# MCU.net
KiCad netlist of a schematic drawn in Altium Designer
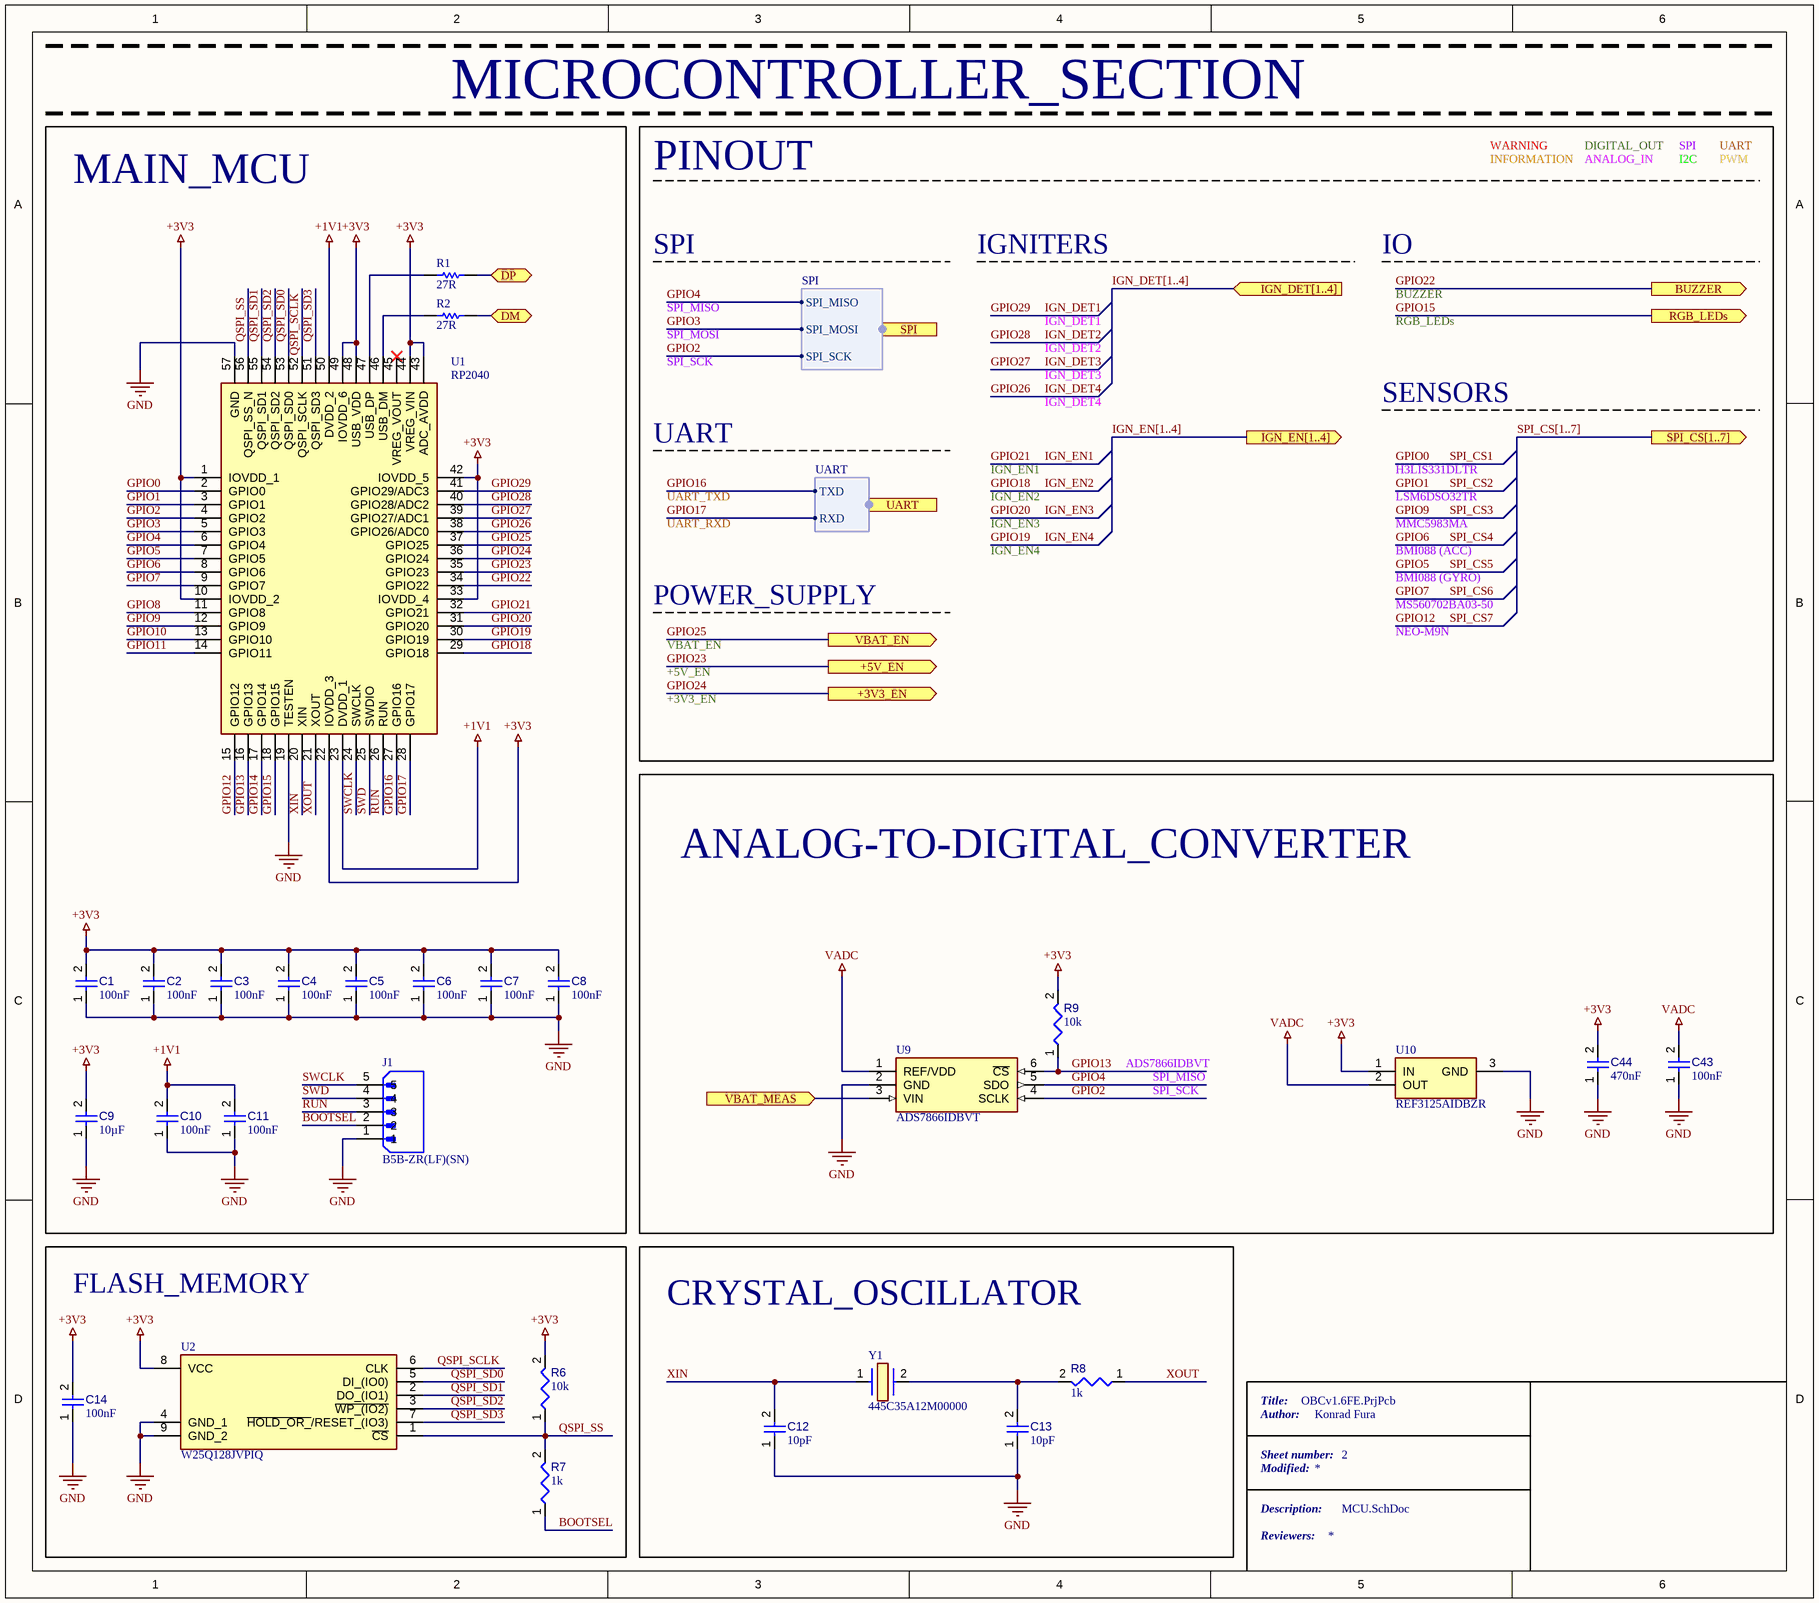
[diagram p0: MCU.SchDoc]

(export (version "E")
  (design (tool "Eeschema 10.0.6"))
  (components
    (comp (ref "C1")
      (value "100nF")
      (footprint "CAPC0402(1005)60_L")
      (description "Chip Capacitor, 100nF +/-20%, 10V, 0402, Thickness 0.6 mm")
      (fields (field (name "TOLERANCE") "20%") (field (name "Comment") "Capacitor 100nF +/-20% 10V 0402"))
      (libsource (lib "PWr in Space team") (part "CAP-NP-2"))
    )
    (comp (ref "C2")
      (value "100nF")
      (footprint "CAPC0402(1005)60_L")
      (description "Chip Capacitor, 100nF +/-20%, 10V, 0402, Thickness 0.6 mm")
      (fields (field (name "TOLERANCE") "20%") (field (name "Comment") "Capacitor 100nF +/-20% 10V 0402"))
      (libsource (lib "PWr in Space team") (part "CAP-NP-2"))
    )
    (comp (ref "C3")
      (value "100nF")
      (footprint "CAPC0402(1005)60_L")
      (description "Chip Capacitor, 100nF +/-20%, 10V, 0402, Thickness 0.6 mm")
      (fields (field (name "TOLERANCE") "20%") (field (name "Comment") "Capacitor 100nF +/-20% 10V 0402"))
      (libsource (lib "PWr in Space team") (part "CAP-NP-2"))
    )
    (comp (ref "C4")
      (value "100nF")
      (footprint "CAPC0402(1005)60_L")
      (description "Chip Capacitor, 100nF +/-20%, 10V, 0402, Thickness 0.6 mm")
      (fields (field (name "TOLERANCE") "20%") (field (name "Comment") "Capacitor 100nF +/-20% 10V 0402"))
      (libsource (lib "PWr in Space team") (part "CAP-NP-2"))
    )
    (comp (ref "C5")
      (value "100nF")
      (footprint "CAPC0402(1005)60_L")
      (description "Chip Capacitor, 100nF +/-20%, 10V, 0402, Thickness 0.6 mm")
      (fields (field (name "TOLERANCE") "20%") (field (name "Comment") "Capacitor 100nF +/-20% 10V 0402"))
      (libsource (lib "PWr in Space team") (part "CAP-NP-2"))
    )
    (comp (ref "C6")
      (value "100nF")
      (footprint "CAPC0402(1005)60_L")
      (description "Chip Capacitor, 100nF +/-20%, 10V, 0402, Thickness 0.6 mm")
      (fields (field (name "TOLERANCE") "20%") (field (name "Comment") "Capacitor 100nF +/-20% 10V 0402"))
      (libsource (lib "PWr in Space team") (part "CAP-NP-2"))
    )
    (comp (ref "C7")
      (value "100nF")
      (footprint "CAPC0402(1005)60_L")
      (description "Chip Capacitor, 100nF +/-20%, 10V, 0402, Thickness 0.6 mm")
      (fields (field (name "TOLERANCE") "20%") (field (name "Comment") "Capacitor 100nF +/-20% 10V 0402"))
      (libsource (lib "PWr in Space team") (part "CAP-NP-2"))
    )
    (comp (ref "C8")
      (value "100nF")
      (footprint "CAPC0402(1005)60_L")
      (description "Chip Capacitor, 100nF +/-20%, 10V, 0402, Thickness 0.6 mm")
      (fields (field (name "TOLERANCE") "20%") (field (name "Comment") "Capacitor 100nF +/-20% 10V 0402"))
      (libsource (lib "PWr in Space team") (part "CAP-NP-2"))
    )
    (comp (ref "C9")
      (value "10µF")
      (footprint "CAPC3216X180X50NL20T25")
      (description "Chip Capacitor, 10 uF, +/- 10%, 16 V, 1206 (3216 Metric)")
      (fields (field (name "TOLERANCE") "10%") (field (name "Comment") "Capacitor 10 uF +/- 10% 16 V 1206"))
      (libsource (lib "PWr in Space team") (part "CAP-NP-2"))
    )
    (comp (ref "C10")
      (value "100nF")
      (footprint "CAPC0402(1005)60_L")
      (description "Chip Capacitor, 100nF +/-20%, 10V, 0402, Thickness 0.6 mm")
      (fields (field (name "TOLERANCE") "20%") (field (name "Comment") "Capacitor 100nF +/-20% 10V 0402"))
      (libsource (lib "PWr in Space team") (part "CAP-NP-2"))
    )
    (comp (ref "C11")
      (value "100nF")
      (footprint "CAPC0402(1005)60_L")
      (description "Chip Capacitor, 100nF +/-20%, 10V, 0402, Thickness 0.6 mm")
      (fields (field (name "TOLERANCE") "20%") (field (name "Comment") "Capacitor 100nF +/-20% 10V 0402"))
      (libsource (lib "PWr in Space team") (part "CAP-NP-2"))
    )
    (comp (ref "C12")
      (value "10pF")
      (footprint "CAPC1005X55X30LL05T10")
      (description "Chip Capacitor, 10 pF, +/- 0.25 pF, 50 V, 0402 (1005 Metric)")
      (fields
        (field (name "TOLERANCE") "0.25%")
        (field (name "Comment") "Capacitor 10 pF +/- 0.25 pF 50 V 0402")
      )
      (libsource (lib "PWr in Space team") (part "CAP-NP-2"))
    )
    (comp (ref "C13")
      (value "10pF")
      (footprint "CAPC1005X55X30LL05T10")
      (description "Chip Capacitor, 10 pF, +/- 0.25 pF, 50 V, 0402 (1005 Metric)")
      (fields
        (field (name "TOLERANCE") "0.25%")
        (field (name "Comment") "Capacitor 10 pF +/- 0.25 pF 50 V 0402")
      )
      (libsource (lib "PWr in Space team") (part "CAP-NP-2"))
    )
    (comp (ref "C14")
      (value "100nF")
      (footprint "CAPC0402(1005)60_L")
      (description "Chip Capacitor, 100nF +/-20%, 10V, 0402, Thickness 0.6 mm")
      (fields (field (name "TOLERANCE") "20%") (field (name "Comment") "Capacitor 100nF +/-20% 10V 0402"))
      (libsource (lib "PWr in Space team") (part "CAP-NP-2"))
    )
    (comp (ref "C43")
      (value "100nF")
      (footprint "CAPC0402(1005)60_L")
      (description "Chip Capacitor, 100nF +/-20%, 10V, 0402, Thickness 0.6 mm")
      (fields (field (name "TOLERANCE") "20%") (field (name "Comment") "Capacitor 100nF +/-20% 10V 0402"))
      (libsource (lib "PWr in Space team") (part "CAP-NP-2"))
    )
    (comp (ref "C44")
      (value "470nF")
      (footprint "CAPC0402(1005)60_L")
      (description "Chip Capacitor, 470nF +/-40%, 10V, 0402, Thickness 0.6 mm")
      (fields (field (name "TOLERANCE") "20%") (field (name "Comment") "Capacitor 470nF +/-40% 10V 0402"))
      (libsource (lib "PWr in Space team") (part "CAP-NP-2"))
    )
    (comp (ref "J1")
      (value "B5B-ZR(LF)(SN)")
      (footprint "JST_B5B-ZR(LF)(SN)")
      (fields (field (name "MF") "{'manufacturer': u'JST'}"))
      (libsource (lib "SnapEDA_Library") (part "B5B-ZR(LF)(SN)"))
    )
    (comp (ref "R1")
      (value "27R")
      (footprint "RESC1005X40X25NL05T05")
      (fields (field (name "MANUFACTURER") "Vishay Dale") (field (name "PART NUMBER") "CRCW040227R0JNED"))
      (libsource (lib "Altium Content Vault") (part "RES"))
    )
    (comp (ref "R2")
      (value "27R")
      (footprint "RESC1005X40X25NL05T05")
      (fields (field (name "MANUFACTURER") "Vishay Dale") (field (name "PART NUMBER") "CRCW040227R0JNED"))
      (libsource (lib "Altium Content Vault") (part "RES"))
    )
    (comp (ref "R6")
      (value "10k")
      (footprint "RESC0402(1005)_L")
      (description "Chip Resistor, 10 kOhms, +/-1 %, 63 mW, -55 to 125 degC, 0402")
      (fields (field (name "POWER") "63mW") (field (name "TOLERANCE") "1%"))
      (libsource (lib "PWr in Space team") (part "RES-2"))
    )
    (comp (ref "R7")
      (value "1k")
      (footprint "RESC0402(1005)_L")
      (description "Chip Resistor, 1 kOhms, +/-5 %, 63 mW, -55 to 155 degC, 0402")
      (fields (field (name "TOLERANCE") "5%") (field (name "POWER") "63mW"))
      (libsource (lib "PWr in Space team") (part "RES-2"))
    )
    (comp (ref "R8")
      (value "1k")
      (footprint "RESC0402(1005)_L")
      (description "Chip Resistor, 1 kOhms, +/-5 %, 63 mW, -55 to 155 degC, 0402")
      (fields (field (name "TOLERANCE") "5%") (field (name "POWER") "63mW"))
      (libsource (lib "PWr in Space team") (part "RES-2"))
    )
    (comp (ref "R9")
      (value "10k")
      (footprint "RESC0402(1005)_L")
      (description "Chip Resistor, 10 kOhms, +/-1 %, 63 mW, -55 to 125 degC, 0402")
      (fields (field (name "POWER") "63mW") (field (name "TOLERANCE") "1%"))
      (libsource (lib "PWr in Space team") (part "RES-2"))
    )
    (comp (ref "U1")
      (value "RP2040")
      (footprint "QFN40P700X700X90-57N-D")
      (description "Integrated Circuit")
      (fields
        (field (name "MANUFACTURER_PART_NUMBER") "RPI Chip RP2040-10-10")
        (field (name "MOUSER PART NUMBER") "358-RP2040CHIP-10-10")
      )
      (libsource (lib "PWr in Space team") (part "RPI_Chip_RP2040-10-10"))
    )
    (comp (ref "U2")
      (value "W25Q128JVPIQ")
      (footprint "SamacSys:SON127P600X500X80-9N-D")
      (description "Integrated Circuit")
      (fields (field (name "MOUSER PART NUMBER") "454-W25Q128JVPIQ"))
      (libsource (lib "*") (part "W25Q128JVPIQ"))
    )
    (comp (ref "U9")
      (value "ADS7866IDBVT")
      (footprint "SamacSys:SOT95P280X145-6N")
      (description "Integrated Circuit")
      (fields (field (name "MOUSER PART NUMBER") "595-ADS7866IDBVT"))
      (libsource (lib "*") (part "ADS7866IDBVT"))
    )
    (comp (ref "U10")
      (value "REF3125AIDBZR")
      (footprint "SamacSys:SOT95P237X112-3N")
      (description "Power Supply")
      (fields (field (name "MOUSER PART NUMBER") "595-REF3125AIDBZR"))
      (libsource (lib "*") (part "REF3125AIDBZR"))
    )
    (comp (ref "Y1")
      (value "445C35A12M00000")
      (footprint "SamacSys:445I23D24M00000")
      (description "Crystal or Oscillator")
      (fields
        (field (name "MANUFACTURER_PART_NUMBER") "445I23D12M00000")
        (field (name "MOUSER PART NUMBER") "774-445I23D12M00000")
      )
      (libsource (lib "*") (part "445I23D12M00000"))
    )
  )
  (nets
    (net (code "3") (name "+1V1") (class "Default")
      (node (ref "C10") (pin "2") (pinfunction "2_2") (pintype "passive"))
      (node (ref "C11") (pin "2") (pinfunction "2_2") (pintype "passive"))
      (node (ref "U1") (pin "23") (pinfunction "DVDD_1_23") (pintype "passive"))
      (node (ref "U1") (pin "50") (pinfunction "DVDD_2_50") (pintype "passive"))
    )
    (net (code "4") (name "+3V3") (class "Default")
      (node (ref "C1") (pin "2") (pinfunction "2_2") (pintype "passive"))
      (node (ref "C14") (pin "2") (pinfunction "2_2") (pintype "passive"))
      (node (ref "C2") (pin "2") (pinfunction "2_2") (pintype "passive"))
      (node (ref "C3") (pin "2") (pinfunction "2_2") (pintype "passive"))
      (node (ref "C4") (pin "2") (pinfunction "2_2") (pintype "passive"))
      (node (ref "C44") (pin "2") (pinfunction "2_2") (pintype "passive"))
      (node (ref "C5") (pin "2") (pinfunction "2_2") (pintype "passive"))
      (node (ref "C6") (pin "2") (pinfunction "2_2") (pintype "passive"))
      (node (ref "C7") (pin "2") (pinfunction "2_2") (pintype "passive"))
      (node (ref "C8") (pin "2") (pinfunction "2_2") (pintype "passive"))
      (node (ref "C9") (pin "2") (pinfunction "2_2") (pintype "passive"))
      (node (ref "R6") (pin "2") (pinfunction "2_2") (pintype "passive"))
      (node (ref "R9") (pin "2") (pinfunction "2_2") (pintype "passive"))
      (node (ref "U1") (pin "1") (pinfunction "IOVDD_1_1") (pintype "passive"))
      (node (ref "U1") (pin "10") (pinfunction "IOVDD_2_10") (pintype "passive"))
      (node (ref "U1") (pin "22") (pinfunction "IOVDD_3_22") (pintype "passive"))
      (node (ref "U1") (pin "33") (pinfunction "IOVDD_4_33") (pintype "passive"))
      (node (ref "U1") (pin "42") (pinfunction "IOVDD_5_42") (pintype "passive"))
      (node (ref "U1") (pin "43") (pinfunction "ADC_AVDD_43") (pintype "passive"))
      (node (ref "U1") (pin "44") (pinfunction "VREG_VIN_44") (pintype "passive"))
      (node (ref "U1") (pin "48") (pinfunction "USB_VDD_48") (pintype "passive"))
      (node (ref "U1") (pin "49") (pinfunction "IOVDD_6_49") (pintype "passive"))
      (node (ref "U10") (pin "1") (pinfunction "IN_1") (pintype "passive"))
      (node (ref "U2") (pin "8") (pinfunction "VCC_8") (pintype "passive"))
    )
    (net (code "5") (name "/BOOTSEL") (class "Default")
      (node (ref "J1") (pin "2") (pinfunction "2_2") (pintype "passive"))
      (node (ref "R7") (pin "1") (pinfunction "1_1") (pintype "passive"))
    )
    (net (code "6") (name "/DM") (class "Default")
      (node (ref "R2") (pin "2") (pinfunction "2_2") (pintype "passive"))
    )
    (net (code "7") (name "/DP") (class "Default")
      (node (ref "R1") (pin "2") (pinfunction "2_2") (pintype "passive"))
    )
    (net (code "8") (name "/GPIO2") (class "Default")
      (node (ref "U1") (pin "4") (pinfunction "GPIO2_4") (pintype "passive"))
      (node (ref "U9") (pin "4") (pinfunction "SCLK_4") (pintype "input"))
    )
    (net (code "9") (name "/GPIO3") (class "Default")
      (node (ref "U1") (pin "5") (pinfunction "GPIO3_5") (pintype "passive"))
    )
    (net (code "10") (name "/GPIO4") (class "Default")
      (node (ref "U1") (pin "6") (pinfunction "GPIO4_6") (pintype "passive"))
      (node (ref "U9") (pin "5") (pinfunction "SDO_5") (pintype "output"))
    )
    (net (code "11") (name "/GPIO8") (class "Default")
      (node (ref "U1") (pin "11") (pinfunction "GPIO8_11") (pintype "passive"))
    )
    (net (code "12") (name "/GPIO10") (class "Default")
      (node (ref "U1") (pin "13") (pinfunction "GPIO10_13") (pintype "passive"))
    )
    (net (code "13") (name "/GPIO11") (class "Default")
      (node (ref "U1") (pin "14") (pinfunction "GPIO11_14") (pintype "passive"))
    )
    (net (code "14") (name "/GPIO13") (class "Default")
      (node (ref "R9") (pin "1") (pinfunction "1_1") (pintype "passive"))
      (node (ref "U1") (pin "16") (pinfunction "GPIO13_16") (pintype "passive"))
      (node (ref "U9") (pin "6") (pinfunction "~{CS}_6") (pintype "input"))
    )
    (net (code "15") (name "/GPIO14") (class "Default")
      (node (ref "U1") (pin "17") (pinfunction "GPIO14_17") (pintype "passive"))
    )
    (net (code "16") (name "/GPIO15") (class "Default")
      (node (ref "U1") (pin "18") (pinfunction "GPIO15_18") (pintype "passive"))
    )
    (net (code "17") (name "/GPIO16") (class "Default")
      (node (ref "U1") (pin "27") (pinfunction "GPIO16_27") (pintype "passive"))
    )
    (net (code "18") (name "/GPIO17") (class "Default")
      (node (ref "U1") (pin "28") (pinfunction "GPIO17_28") (pintype "passive"))
    )
    (net (code "19") (name "/GPIO22") (class "Default")
      (node (ref "U1") (pin "34") (pinfunction "GPIO22_34") (pintype "passive"))
    )
    (net (code "20") (name "/GPIO23") (class "Default")
      (node (ref "U1") (pin "35") (pinfunction "GPIO23_35") (pintype "passive"))
    )
    (net (code "21") (name "/GPIO24") (class "Default")
      (node (ref "U1") (pin "36") (pinfunction "GPIO24_36") (pintype "passive"))
    )
    (net (code "22") (name "/GPIO25") (class "Default")
      (node (ref "U1") (pin "37") (pinfunction "GPIO25_37") (pintype "passive"))
    )
    (net (code "23") (name "/IGN_DET1") (class "Default")
      (node (ref "U1") (pin "41") (pinfunction "GPIO29/ADC3_41") (pintype "passive"))
    )
    (net (code "24") (name "/IGN_DET2") (class "Default")
      (node (ref "U1") (pin "40") (pinfunction "GPIO28/ADC2_40") (pintype "passive"))
    )
    (net (code "25") (name "/IGN_DET3") (class "Default")
      (node (ref "U1") (pin "39") (pinfunction "GPIO27/ADC1_39") (pintype "passive"))
    )
    (net (code "26") (name "/IGN_DET4") (class "Default")
      (node (ref "U1") (pin "38") (pinfunction "GPIO26/ADC0_38") (pintype "passive"))
    )
    (net (code "28") (name "/IGN_EN1") (class "Default")
      (node (ref "U1") (pin "32") (pinfunction "GPIO21_32") (pintype "passive"))
    )
    (net (code "29") (name "/IGN_EN2") (class "Default")
      (node (ref "U1") (pin "29") (pinfunction "GPIO18_29") (pintype "passive"))
    )
    (net (code "30") (name "/IGN_EN3") (class "Default")
      (node (ref "U1") (pin "31") (pinfunction "GPIO20_31") (pintype "passive"))
    )
    (net (code "31") (name "/IGN_EN4") (class "Default")
      (node (ref "U1") (pin "30") (pinfunction "GPIO19_30") (pintype "passive"))
    )
    (net (code "33") (name "/QSPI_SCLK") (class "Default")
      (node (ref "U1") (pin "52") (pinfunction "QSPI_SCLK_52") (pintype "passive"))
      (node (ref "U2") (pin "6") (pinfunction "CLK_6") (pintype "passive"))
    )
    (net (code "34") (name "/QSPI_SD0") (class "Default")
      (node (ref "U1") (pin "53") (pinfunction "QSPI_SD0_53") (pintype "passive"))
      (node (ref "U2") (pin "5") (pinfunction "DI_(IO0)_5") (pintype "passive"))
    )
    (net (code "35") (name "/QSPI_SD1") (class "Default")
      (node (ref "U1") (pin "55") (pinfunction "QSPI_SD1_55") (pintype "passive"))
      (node (ref "U2") (pin "2") (pinfunction "DO_(IO1)_2") (pintype "passive"))
    )
    (net (code "36") (name "/QSPI_SD2") (class "Default")
      (node (ref "U1") (pin "54") (pinfunction "QSPI_SD2_54") (pintype "passive"))
      (node (ref "U2") (pin "3") (pinfunction "~{WP_(IO2)}_3") (pintype "passive"))
    )
    (net (code "37") (name "/QSPI_SD3") (class "Default")
      (node (ref "U1") (pin "51") (pinfunction "QSPI_SD3_51") (pintype "passive"))
      (node (ref "U2") (pin "7") (pinfunction "~{HOLD_OR_}/RESET_(IO3)_7") (pintype "passive"))
    )
    (net (code "38") (name "/QSPI_SS") (class "Default")
      (node (ref "R6") (pin "1") (pinfunction "1_1") (pintype "passive"))
      (node (ref "R7") (pin "2") (pinfunction "2_2") (pintype "passive"))
      (node (ref "U1") (pin "56") (pinfunction "QSPI_SS_N_56") (pintype "passive"))
      (node (ref "U2") (pin "1") (pinfunction "~{CS}_1") (pintype "passive"))
    )
    (net (code "39") (name "/RUN") (class "Default")
      (node (ref "J1") (pin "3") (pinfunction "3_3") (pintype "passive"))
      (node (ref "U1") (pin "26") (pinfunction "RUN_26") (pintype "passive"))
    )
    (net (code "40") (name "/SPI_CS1") (class "Default")
      (node (ref "U1") (pin "2") (pinfunction "GPIO0_2") (pintype "passive"))
    )
    (net (code "41") (name "/SPI_CS2") (class "Default")
      (node (ref "U1") (pin "3") (pinfunction "GPIO1_3") (pintype "passive"))
    )
    (net (code "42") (name "/SPI_CS3") (class "Default")
      (node (ref "U1") (pin "12") (pinfunction "GPIO9_12") (pintype "passive"))
    )
    (net (code "43") (name "/SPI_CS4") (class "Default")
      (node (ref "U1") (pin "8") (pinfunction "GPIO6_8") (pintype "passive"))
    )
    (net (code "44") (name "/SPI_CS5") (class "Default")
      (node (ref "U1") (pin "7") (pinfunction "GPIO5_7") (pintype "passive"))
    )
    (net (code "45") (name "/SPI_CS6") (class "Default")
      (node (ref "U1") (pin "9") (pinfunction "GPIO7_9") (pintype "passive"))
    )
    (net (code "46") (name "/SPI_CS7") (class "Default")
      (node (ref "U1") (pin "15") (pinfunction "GPIO12_15") (pintype "passive"))
    )
    (net (code "48") (name "/SWCLK") (class "Default")
      (node (ref "J1") (pin "5") (pinfunction "5_5") (pintype "passive"))
      (node (ref "U1") (pin "24") (pinfunction "SWCLK_24") (pintype "passive"))
    )
    (net (code "49") (name "/SWD") (class "Default")
      (node (ref "J1") (pin "4") (pinfunction "4_4") (pintype "passive"))
      (node (ref "U1") (pin "25") (pinfunction "SWDIO_25") (pintype "passive"))
    )
    (net (code "50") (name "/VBAT_MEAS") (class "Default")
      (node (ref "U9") (pin "3") (pinfunction "VIN_3") (pintype "input"))
    )
    (net (code "51") (name "/XIN") (class "Default")
      (node (ref "C12") (pin "2") (pinfunction "2_2") (pintype "passive"))
      (node (ref "U1") (pin "20") (pinfunction "XIN_20") (pintype "passive"))
      (node (ref "Y1") (pin "1") (pinfunction "1_1") (pintype "passive"))
    )
    (net (code "52") (name "/XOUT") (class "Default")
      (node (ref "R8") (pin "1") (pinfunction "1_1") (pintype "passive"))
      (node (ref "U1") (pin "21") (pinfunction "XOUT_21") (pintype "passive"))
    )
    (net (code "55") (name "GND") (class "Default")
      (node (ref "C1") (pin "1") (pinfunction "1_1") (pintype "passive"))
      (node (ref "C10") (pin "1") (pinfunction "1_1") (pintype "passive"))
      (node (ref "C11") (pin "1") (pinfunction "1_1") (pintype "passive"))
      (node (ref "C12") (pin "1") (pinfunction "1_1") (pintype "passive"))
      (node (ref "C13") (pin "1") (pinfunction "1_1") (pintype "passive"))
      (node (ref "C14") (pin "1") (pinfunction "1_1") (pintype "passive"))
      (node (ref "C2") (pin "1") (pinfunction "1_1") (pintype "passive"))
      (node (ref "C3") (pin "1") (pinfunction "1_1") (pintype "passive"))
      (node (ref "C4") (pin "1") (pinfunction "1_1") (pintype "passive"))
      (node (ref "C43") (pin "1") (pinfunction "1_1") (pintype "passive"))
      (node (ref "C44") (pin "1") (pinfunction "1_1") (pintype "passive"))
      (node (ref "C5") (pin "1") (pinfunction "1_1") (pintype "passive"))
      (node (ref "C6") (pin "1") (pinfunction "1_1") (pintype "passive"))
      (node (ref "C7") (pin "1") (pinfunction "1_1") (pintype "passive"))
      (node (ref "C8") (pin "1") (pinfunction "1_1") (pintype "passive"))
      (node (ref "C9") (pin "1") (pinfunction "1_1") (pintype "passive"))
      (node (ref "J1") (pin "1") (pinfunction "1_1") (pintype "passive"))
      (node (ref "U1") (pin "19") (pinfunction "TESTEN_19") (pintype "passive"))
      (node (ref "U1") (pin "57") (pinfunction "GND_57") (pintype "passive"))
      (node (ref "U10") (pin "3") (pinfunction "GND_3") (pintype "passive"))
      (node (ref "U2") (pin "4") (pinfunction "GND_1_4") (pintype "passive"))
      (node (ref "U2") (pin "9") (pinfunction "GND_2_9") (pintype "passive"))
      (node (ref "U9") (pin "2") (pinfunction "GND_2") (pintype "power_in"))
    )
    (net (code "56") (name "Net-(C13-Pad2)") (class "Default")
      (node (ref "C13") (pin "2") (pinfunction "2_2") (pintype "passive"))
      (node (ref "R8") (pin "2") (pinfunction "2_2") (pintype "passive"))
      (node (ref "Y1") (pin "2") (pinfunction "2_2") (pintype "passive"))
    )
    (net (code "57") (name "Net-(U1-USB_DM)") (class "Default")
      (node (ref "R2") (pin "1") (pinfunction "1_1") (pintype "passive"))
      (node (ref "U1") (pin "46") (pinfunction "USB_DM_46") (pintype "passive"))
    )
    (net (code "58") (name "Net-(U1-USB_DP)") (class "Default")
      (node (ref "R1") (pin "1") (pinfunction "1_1") (pintype "passive"))
      (node (ref "U1") (pin "47") (pinfunction "USB_DP_47") (pintype "passive"))
    )
    (net (code "59") (name "VADC") (class "Default")
      (node (ref "C43") (pin "2") (pinfunction "2_2") (pintype "passive"))
      (node (ref "U10") (pin "2") (pinfunction "OUT_2") (pintype "passive"))
      (node (ref "U9") (pin "1") (pinfunction "REF/VDD_1") (pintype "power_in"))
    )
    (net (code "60") (name "unconnected-(U1-VREG_VOUT-Pad45)") (class "Default")
      (node (ref "U1") (pin "45") (pinfunction "VREG_VOUT_45") (pintype "passive+no_connect"))
    )
  )
)
